# WiFi.net
KiCad netlist of a schematic drawn in Altium Designer
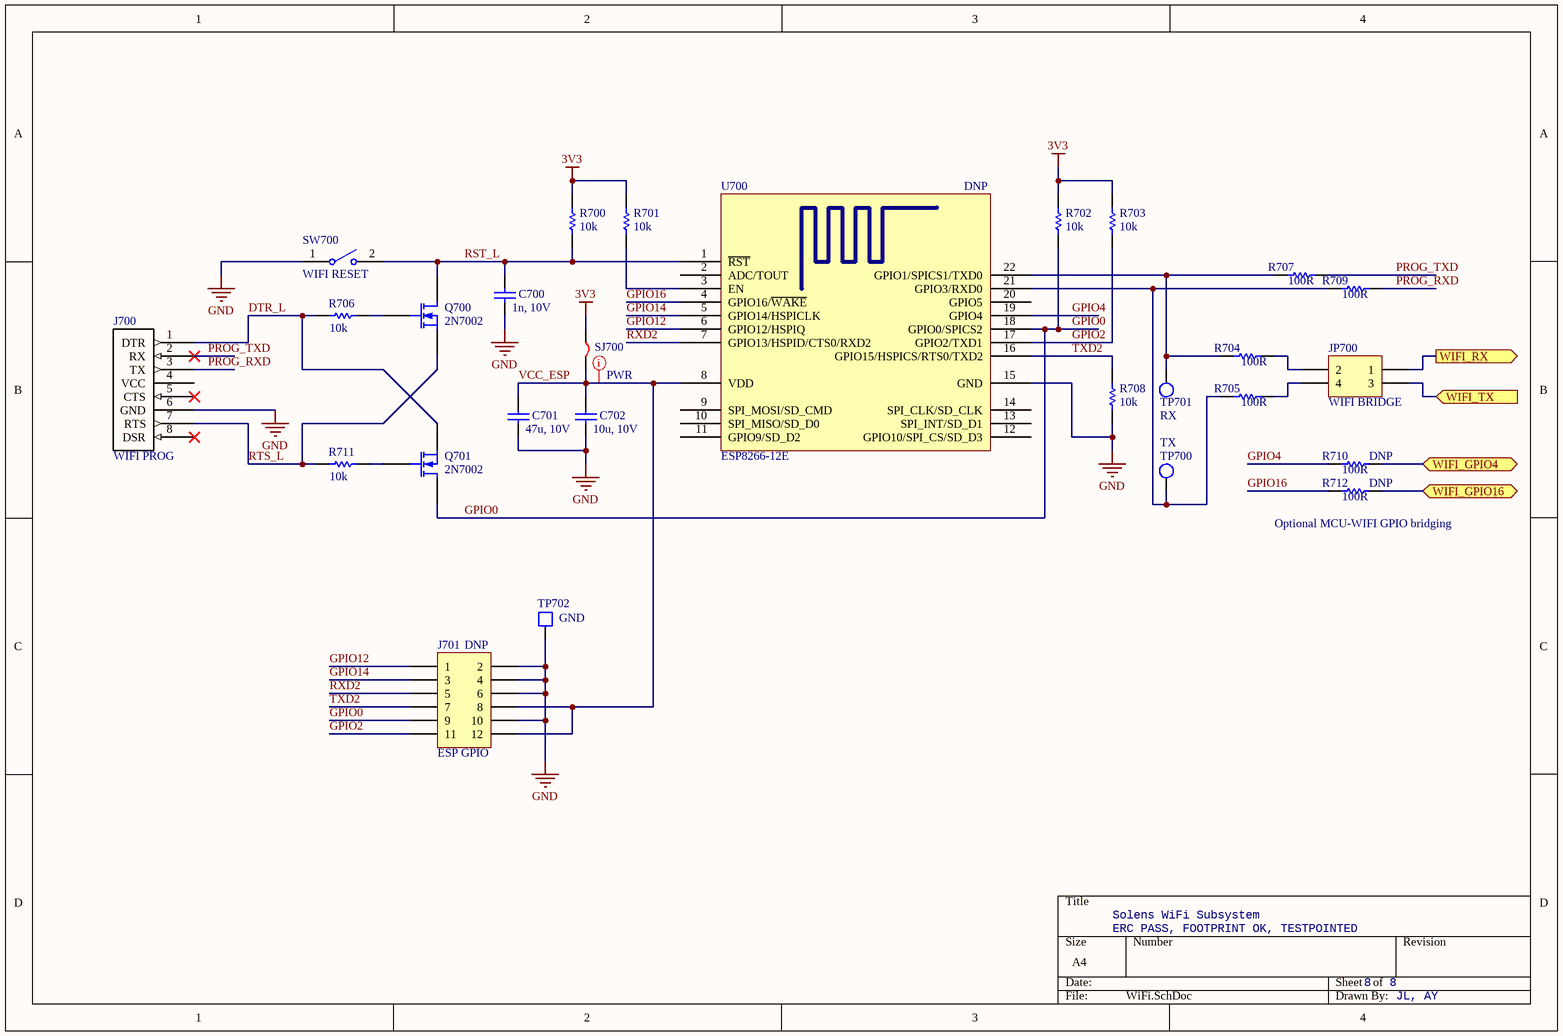
[diagram p0: WiFi.SchDoc]

(export (version "E")
  (design (tool "Eeschema 10.0.6"))
  (components
    (comp (ref "C700")
      (value "1n, 10V")
      (footprint "CAP_0805")
      (description "Capacitor")
      (fields (field (name "Comment") "1n, 16V, 0805"))
      (libsource (lib "Miscellaneous Devices") (part "Cap"))
    )
    (comp (ref "C701")
      (value "47u, 10V")
      (footprint "CAP_1206")
      (description "Capacitor")
      (fields (field (name "Comment") "47u, 10V, 1206"))
      (libsource (lib "Miscellaneous Devices") (part "Cap"))
    )
    (comp (ref "C702")
      (value "10u, 10V")
      (footprint "CAP_1206")
      (description "Capacitor")
      (fields (field (name "Comment") "10u, 10V, 1206"))
      (libsource (lib "Miscellaneous Devices") (part "Cap"))
    )
    (comp (ref "J700")
      (value "HDR_1x8_100TH_THT")
      (footprint "HDR1X8")
      (fields (field (name "FUNCTION") "WIFI PROG"))
      (libsource (lib "Schlib1") (part "HDR_FTDI_EXTENDED"))
    )
    (comp (ref "J701")
      (value "HDR_2x6_100TH_SMT (DNP)")
      (footprint "HDR_100TH_2X6_SMT")
      (description "Header, 6-Pin, Dual row")
      (fields (field (name "DNP") "DNP") (field (name "FUNCTION") "ESP GPIO"))
      (libsource (lib "Miscellaneous Connectors") (part "Header 6X2"))
    )
    (comp (ref "JP700")
      (value "HDR_2x2_100TH_THT")
      (footprint "HDR2X2")
      (description "Header, 2-Pin, Dual row")
      (fields (field (name "FUNCTION") "WIFI BRIDGE"))
      (libsource (lib "Miscellaneous Connectors") (part "Header 2X2"))
    )
    (comp (ref "Q700")
      (value "2N7002, SOT-23")
      (footprint "SOT95P240X100-3N (CMPSH1-4 TR)")
      (description "N-Channel MOSFET")
      (fields (field (name "PARTNUMBER") "2N7002"))
      (libsource (lib "Miscellaneous Devices") (part "MOSFET-N"))
    )
    (comp (ref "Q701")
      (value "2N7002, SOT-23")
      (footprint "SOT95P240X100-3N (CMPSH1-4 TR)")
      (description "N-Channel MOSFET")
      (fields (field (name "PARTNUMBER") "2N7002"))
      (libsource (lib "Miscellaneous Devices") (part "MOSFET-N"))
    )
    (comp (ref "R700")
      (value "10k")
      (footprint "RES_0805")
      (description "Resistor")
      (fields (field (name "Comment") "10k, 1/8W, 0805"))
      (libsource (lib "Miscellaneous Devices") (part "Res1"))
    )
    (comp (ref "R701")
      (value "10k")
      (footprint "RES_0805")
      (description "Resistor")
      (fields (field (name "Comment") "10k, 1/8W, 0805"))
      (libsource (lib "Miscellaneous Devices") (part "Res1"))
    )
    (comp (ref "R702")
      (value "10k")
      (footprint "RES_0805")
      (description "Resistor")
      (fields (field (name "Comment") "10k, 1/8W, 0805"))
      (libsource (lib "Miscellaneous Devices") (part "Res1"))
    )
    (comp (ref "R703")
      (value "10k")
      (footprint "RES_0805")
      (description "Resistor")
      (fields (field (name "Comment") "10k, 1/8W, 0805"))
      (libsource (lib "Miscellaneous Devices") (part "Res1"))
    )
    (comp (ref "R704")
      (value "100R")
      (footprint "RES_0805")
      (description "Resistor")
      (fields (field (name "Comment") "100R, 1/8W, 0805"))
      (libsource (lib "Miscellaneous Devices") (part "Res1"))
    )
    (comp (ref "R705")
      (value "100R")
      (footprint "RES_0805")
      (description "Resistor")
      (fields (field (name "Comment") "100R, 1/8W, 0805"))
      (libsource (lib "Miscellaneous Devices") (part "Res1"))
    )
    (comp (ref "R706")
      (value "10k")
      (footprint "RES_0805")
      (description "Resistor")
      (fields (field (name "Comment") "10k, 1/8W, 0805"))
      (libsource (lib "Miscellaneous Devices") (part "Res1"))
    )
    (comp (ref "R707")
      (value "100R")
      (footprint "RES_0805")
      (description "Resistor")
      (fields (field (name "Comment") "100R, 1/8W, 0805"))
      (libsource (lib "Miscellaneous Devices") (part "Res1"))
    )
    (comp (ref "R708")
      (value "10k")
      (footprint "RES_0805")
      (description "Resistor")
      (fields (field (name "Comment") "10k, 1/8W, 0805"))
      (libsource (lib "Miscellaneous Devices") (part "Res1"))
    )
    (comp (ref "R709")
      (value "100R")
      (footprint "RES_0805")
      (description "Resistor")
      (fields (field (name "Comment") "100R, 1/8W, 0805"))
      (libsource (lib "Miscellaneous Devices") (part "Res1"))
    )
    (comp (ref "R710")
      (value "100R")
      (footprint "RES_0805")
      (description "Resistor")
      (fields (field (name "DNP") "DNP") (field (name "Comment") "100R, 1/8W, 0805 (DNP)"))
      (libsource (lib "Miscellaneous Devices") (part "Res1"))
    )
    (comp (ref "R711")
      (value "10k")
      (footprint "RES_0805")
      (description "Resistor")
      (fields (field (name "Comment") "10k, 1/8W, 0805"))
      (libsource (lib "Miscellaneous Devices") (part "Res1"))
    )
    (comp (ref "R712")
      (value "100R")
      (footprint "RES_0805")
      (description "Resistor")
      (fields (field (name "DNP") "DNP") (field (name "Comment") "100R, 1/8W, 0805 (DNP)"))
      (libsource (lib "Miscellaneous Devices") (part "Res1"))
    )
    (comp (ref "SJ700")
      (value "SJ, 1206 (DNP)")
      (footprint "SJ_1206")
      (description "Solder jumper")
      (libsource (lib "Schlib1") (part "SJ"))
    )
    (comp (ref "SW700")
      (value "434121043816, TACT SPST NO")
      (footprint "4341x10438x6")
      (description "WS-TASV 6.0x3.5 mm SMD")
      (fields
        (field (name "PARTNUMBER") "434121043816")
        (field (name "MANUFACTURER") "Wurth Elektronik")
        (field (name "FUNCTION") "WIFI RESET")
        (field (name "CREATED BY") "Baojun Chen")
      )
      (libsource (lib "ALTIUM-WS-TASV-rev16a") (part "WS-TASV, 434121043816"))
    )
    (comp (ref "TP700")
      (value "TP (DNP)")
      (footprint "TP_SMALL")
      (fields (field (name "VISIBLENETNAME") "TX"))
      (libsource (lib "Schlib1") (part "TP_SMALL"))
    )
    (comp (ref "TP701")
      (value "TP (DNP)")
      (footprint "TP_SMALL")
      (fields (field (name "VISIBLENETNAME") "RX"))
      (libsource (lib "Schlib1") (part "TP_SMALL"))
    )
    (comp (ref "TP702")
      (value "TP (DNP)")
      (footprint "TP_LARGE")
      (fields (field (name "VISIBLENETNAME") "GND"))
      (libsource (lib "Schlib1") (part "TP_LARGE"))
    )
    (comp (ref "U700")
      (value "ESP8266-12E (DNP)")
      (footprint "ESP8266 ESP-12-E")
      (description "ESP8266 ESP-12-E")
      (fields (field (name "PARTNUMBER") "ESP8266-12E") (field (name "DNP") "DNP"))
      (libsource (lib "ESP8266") (part "ESP8266 ESP-12-E"))
    )
  )
  (nets
    (net (code "1") (name "/DTR_L") (class "Default")
      (node (ref "J700") (pin "1") (pinfunction "DTR_1") (pintype "output"))
      (node (ref "Q701") (pin "2") (pinfunction "S_2") (pintype "passive"))
      (node (ref "R706") (pin "2") (pinfunction "2_2") (pintype "passive"))
    )
    (net (code "2") (name "/GPIO0") (class "Default")
      (node (ref "J701") (pin "9") (pinfunction "9_9") (pintype "passive"))
      (node (ref "Q701") (pin "3") (pinfunction "D_3") (pintype "passive"))
      (node (ref "R702") (pin "2") (pinfunction "2_2") (pintype "passive"))
      (node (ref "U700") (pin "18") (pinfunction "GPIO0/SPICS2_18") (pintype "passive"))
    )
    (net (code "3") (name "/GPIO2") (class "Default")
      (node (ref "J701") (pin "11") (pinfunction "11_11") (pintype "passive"))
      (node (ref "R703") (pin "2") (pinfunction "2_2") (pintype "passive"))
      (node (ref "U700") (pin "17") (pinfunction "GPIO2/TXD1_17") (pintype "passive"))
    )
    (net (code "4") (name "/GPIO4") (class "Default")
      (node (ref "R710") (pin "1") (pinfunction "1_1") (pintype "passive"))
      (node (ref "U700") (pin "19") (pinfunction "GPIO4_19") (pintype "passive"))
    )
    (net (code "5") (name "/GPIO12") (class "Default")
      (node (ref "J701") (pin "1") (pinfunction "1_1") (pintype "passive"))
      (node (ref "U700") (pin "6") (pinfunction "GPIO12/HSPIQ_6") (pintype "passive"))
    )
    (net (code "6") (name "/GPIO14") (class "Default")
      (node (ref "J701") (pin "3") (pinfunction "3_3") (pintype "passive"))
      (node (ref "U700") (pin "5") (pinfunction "GPIO14/HSPICLK_5") (pintype "passive"))
    )
    (net (code "7") (name "/GPIO16") (class "Default")
      (node (ref "R712") (pin "1") (pinfunction "1_1") (pintype "passive"))
      (node (ref "U700") (pin "4") (pinfunction "GPIO16/~{WAKE}_4") (pintype "passive"))
    )
    (net (code "8") (name "/PROG_RXD") (class "Default")
      (node (ref "J700") (pin "3") (pinfunction "TX_3") (pintype "output"))
      (node (ref "R709") (pin "2") (pinfunction "2_2") (pintype "passive"))
    )
    (net (code "9") (name "/PROG_TXD") (class "Default")
      (node (ref "J700") (pin "2") (pinfunction "RX_2") (pintype "input"))
      (node (ref "R707") (pin "2") (pinfunction "2_2") (pintype "passive"))
    )
    (net (code "10") (name "/RST_L") (class "Default")
      (node (ref "C700") (pin "1") (pinfunction "1_1") (pintype "passive"))
      (node (ref "Q700") (pin "3") (pinfunction "D_3") (pintype "passive"))
      (node (ref "R700") (pin "1") (pinfunction "1_1") (pintype "passive"))
      (node (ref "SW700") (pin "2") (pinfunction "2_2") (pintype "passive"))
      (node (ref "U700") (pin "1") (pinfunction "~{RST}_1") (pintype "passive"))
    )
    (net (code "11") (name "/RTS_L") (class "Default")
      (node (ref "J700") (pin "7") (pinfunction "RTS_7") (pintype "output"))
      (node (ref "Q700") (pin "2") (pinfunction "S_2") (pintype "passive"))
      (node (ref "R711") (pin "2") (pinfunction "2_2") (pintype "passive"))
    )
    (net (code "12") (name "/RXD2") (class "Default")
      (node (ref "J701") (pin "5") (pinfunction "5_5") (pintype "passive"))
      (node (ref "U700") (pin "7") (pinfunction "GPIO13/HSPID/CTS0/RXD2_7") (pintype "passive"))
    )
    (net (code "13") (name "/TXD2") (class "Default")
      (node (ref "J701") (pin "7") (pinfunction "7_7") (pintype "passive"))
      (node (ref "R708") (pin "2") (pinfunction "2_2") (pintype "passive"))
      (node (ref "U700") (pin "16") (pinfunction "GPIO15/HSPICS/RTS0/TXD2_16") (pintype "passive"))
    )
    (net (code "14") (name "/VCC_ESP") (class "Default")
      (node (ref "C701") (pin "1") (pinfunction "1_1") (pintype "passive"))
      (node (ref "C702") (pin "1") (pinfunction "1_1") (pintype "passive"))
      (node (ref "J701") (pin "12") (pinfunction "12_12") (pintype "passive"))
      (node (ref "J701") (pin "8") (pinfunction "8_8") (pintype "passive"))
      (node (ref "SJ700") (pin "2") (pinfunction "2_2") (pintype "passive"))
      (node (ref "U700") (pin "8") (pinfunction "VDD_8") (pintype "passive"))
    )
    (net (code "15") (name "/WIFI_GPIO4") (class "Default")
      (node (ref "R710") (pin "2") (pinfunction "2_2") (pintype "passive"))
    )
    (net (code "16") (name "/WIFI_GPIO16") (class "Default")
      (node (ref "R712") (pin "2") (pinfunction "2_2") (pintype "passive"))
    )
    (net (code "17") (name "/WIFI_RX") (class "Default")
      (node (ref "JP700") (pin "1") (pinfunction "1_1") (pintype "passive"))
    )
    (net (code "18") (name "/WIFI_TX") (class "Default")
      (node (ref "JP700") (pin "3") (pinfunction "3_3") (pintype "passive"))
    )
    (net (code "19") (name "3V3") (class "Default")
      (node (ref "R700") (pin "2") (pinfunction "2_2") (pintype "passive"))
      (node (ref "R701") (pin "2") (pinfunction "2_2") (pintype "passive"))
      (node (ref "R702") (pin "1") (pinfunction "1_1") (pintype "passive"))
      (node (ref "R703") (pin "1") (pinfunction "1_1") (pintype "passive"))
      (node (ref "SJ700") (pin "1") (pinfunction "1_1") (pintype "passive"))
    )
    (net (code "20") (name "GND") (class "Default")
      (node (ref "C700") (pin "2") (pinfunction "2_2") (pintype "passive"))
      (node (ref "C701") (pin "2") (pinfunction "2_2") (pintype "passive"))
      (node (ref "C702") (pin "2") (pinfunction "2_2") (pintype "passive"))
      (node (ref "J700") (pin "6") (pinfunction "GND_6") (pintype "power_in"))
      (node (ref "J701") (pin "10") (pinfunction "10_10") (pintype "passive"))
      (node (ref "J701") (pin "2") (pinfunction "2_2") (pintype "passive"))
      (node (ref "J701") (pin "4") (pinfunction "4_4") (pintype "passive"))
      (node (ref "J701") (pin "6") (pinfunction "6_6") (pintype "passive"))
      (node (ref "R708") (pin "1") (pinfunction "1_1") (pintype "passive"))
      (node (ref "SW700") (pin "1") (pinfunction "1_1") (pintype "passive"))
      (node (ref "TP702") (pin "1") (pinfunction "1_1") (pintype "passive"))
      (node (ref "U700") (pin "15") (pinfunction "GND_15") (pintype "passive"))
    )
    (net (code "21") (name "Net-(JP700-Pad2)") (class "Default")
      (node (ref "JP700") (pin "2") (pinfunction "2_2") (pintype "passive"))
      (node (ref "R704") (pin "2") (pinfunction "2_2") (pintype "passive"))
    )
    (net (code "22") (name "Net-(JP700-Pad4)") (class "Default")
      (node (ref "JP700") (pin "4") (pinfunction "4_4") (pintype "passive"))
      (node (ref "R705") (pin "2") (pinfunction "2_2") (pintype "passive"))
    )
    (net (code "23") (name "Net-(Q700-G)") (class "Default")
      (node (ref "Q700") (pin "1") (pinfunction "G_1") (pintype "passive"))
      (node (ref "R706") (pin "1") (pinfunction "1_1") (pintype "passive"))
    )
    (net (code "24") (name "Net-(Q701-G)") (class "Default")
      (node (ref "Q701") (pin "1") (pinfunction "G_1") (pintype "passive"))
      (node (ref "R711") (pin "1") (pinfunction "1_1") (pintype "passive"))
    )
    (net (code "25") (name "Net-(U700-EN)") (class "Default")
      (node (ref "R701") (pin "1") (pinfunction "1_1") (pintype "passive"))
      (node (ref "U700") (pin "3") (pinfunction "EN_3") (pintype "passive"))
    )
    (net (code "26") (name "Net-(U700-GPIO1{slash}SPICS1{slash}TXD0)") (class "Default")
      (node (ref "R704") (pin "1") (pinfunction "1_1") (pintype "passive"))
      (node (ref "R707") (pin "1") (pinfunction "1_1") (pintype "passive"))
      (node (ref "TP701") (pin "1") (pinfunction "1_1") (pintype "passive"))
      (node (ref "U700") (pin "22") (pinfunction "GPIO1/SPICS1/TXD0_22") (pintype "passive"))
    )
    (net (code "27") (name "Net-(U700-GPIO3{slash}RXD0)") (class "Default")
      (node (ref "R705") (pin "1") (pinfunction "1_1") (pintype "passive"))
      (node (ref "R709") (pin "1") (pinfunction "1_1") (pintype "passive"))
      (node (ref "TP700") (pin "1") (pinfunction "1_1") (pintype "passive"))
      (node (ref "U700") (pin "21") (pinfunction "GPIO3/RXD0_21") (pintype "passive"))
    )
    (net (code "28") (name "unconnected-(J700-CTS-Pad5)") (class "Default")
      (node (ref "J700") (pin "5") (pinfunction "CTS_5") (pintype "input+no_connect"))
    )
    (net (code "29") (name "unconnected-(J700-DSR-Pad8)") (class "Default")
      (node (ref "J700") (pin "8") (pinfunction "DSR_8") (pintype "input+no_connect"))
    )
    (net (code "30") (name "unconnected-(J700-VCC-Pad4)") (class "Default")
      (node (ref "J700") (pin "4") (pinfunction "VCC_4") (pintype "power_in"))
    )
    (net (code "31") (name "unconnected-(U700-ADC{slash}TOUT-Pad2)") (class "Default")
      (node (ref "U700") (pin "2") (pinfunction "ADC/TOUT_2") (pintype "passive"))
    )
    (net (code "32") (name "unconnected-(U700-GPIO5-Pad20)") (class "Default")
      (node (ref "U700") (pin "20") (pinfunction "GPIO5_20") (pintype "passive"))
    )
    (net (code "33") (name "unconnected-(U700-GPIO9{slash}SD_D2-Pad11)") (class "Default")
      (node (ref "U700") (pin "11") (pinfunction "GPIO9/SD_D2_11") (pintype "passive"))
    )
    (net (code "34") (name "unconnected-(U700-GPIO10{slash}SPI_CS{slash}SD_D3-Pad12)") (class "Default")
      (node (ref "U700") (pin "12") (pinfunction "GPIO10/SPI_CS/SD_D3_12") (pintype "passive"))
    )
    (net (code "35") (name "unconnected-(U700-SPI_CLK{slash}SD_CLK-Pad14)") (class "Default")
      (node (ref "U700") (pin "14") (pinfunction "SPI_CLK/SD_CLK_14") (pintype "passive"))
    )
    (net (code "36") (name "unconnected-(U700-SPI_INT{slash}SD_D1-Pad13)") (class "Default")
      (node (ref "U700") (pin "13") (pinfunction "SPI_INT/SD_D1_13") (pintype "passive"))
    )
    (net (code "37") (name "unconnected-(U700-SPI_MISO{slash}SD_D0-Pad10)") (class "Default")
      (node (ref "U700") (pin "10") (pinfunction "SPI_MISO/SD_D0_10") (pintype "passive"))
    )
    (net (code "38") (name "unconnected-(U700-SPI_MOSI{slash}SD_CMD-Pad9)") (class "Default")
      (node (ref "U700") (pin "9") (pinfunction "SPI_MOSI/SD_CMD_9") (pintype "passive"))
    )
  )
)
